# FMB_MOS.net
KiCad netlist of a schematic drawn in Altium Designer
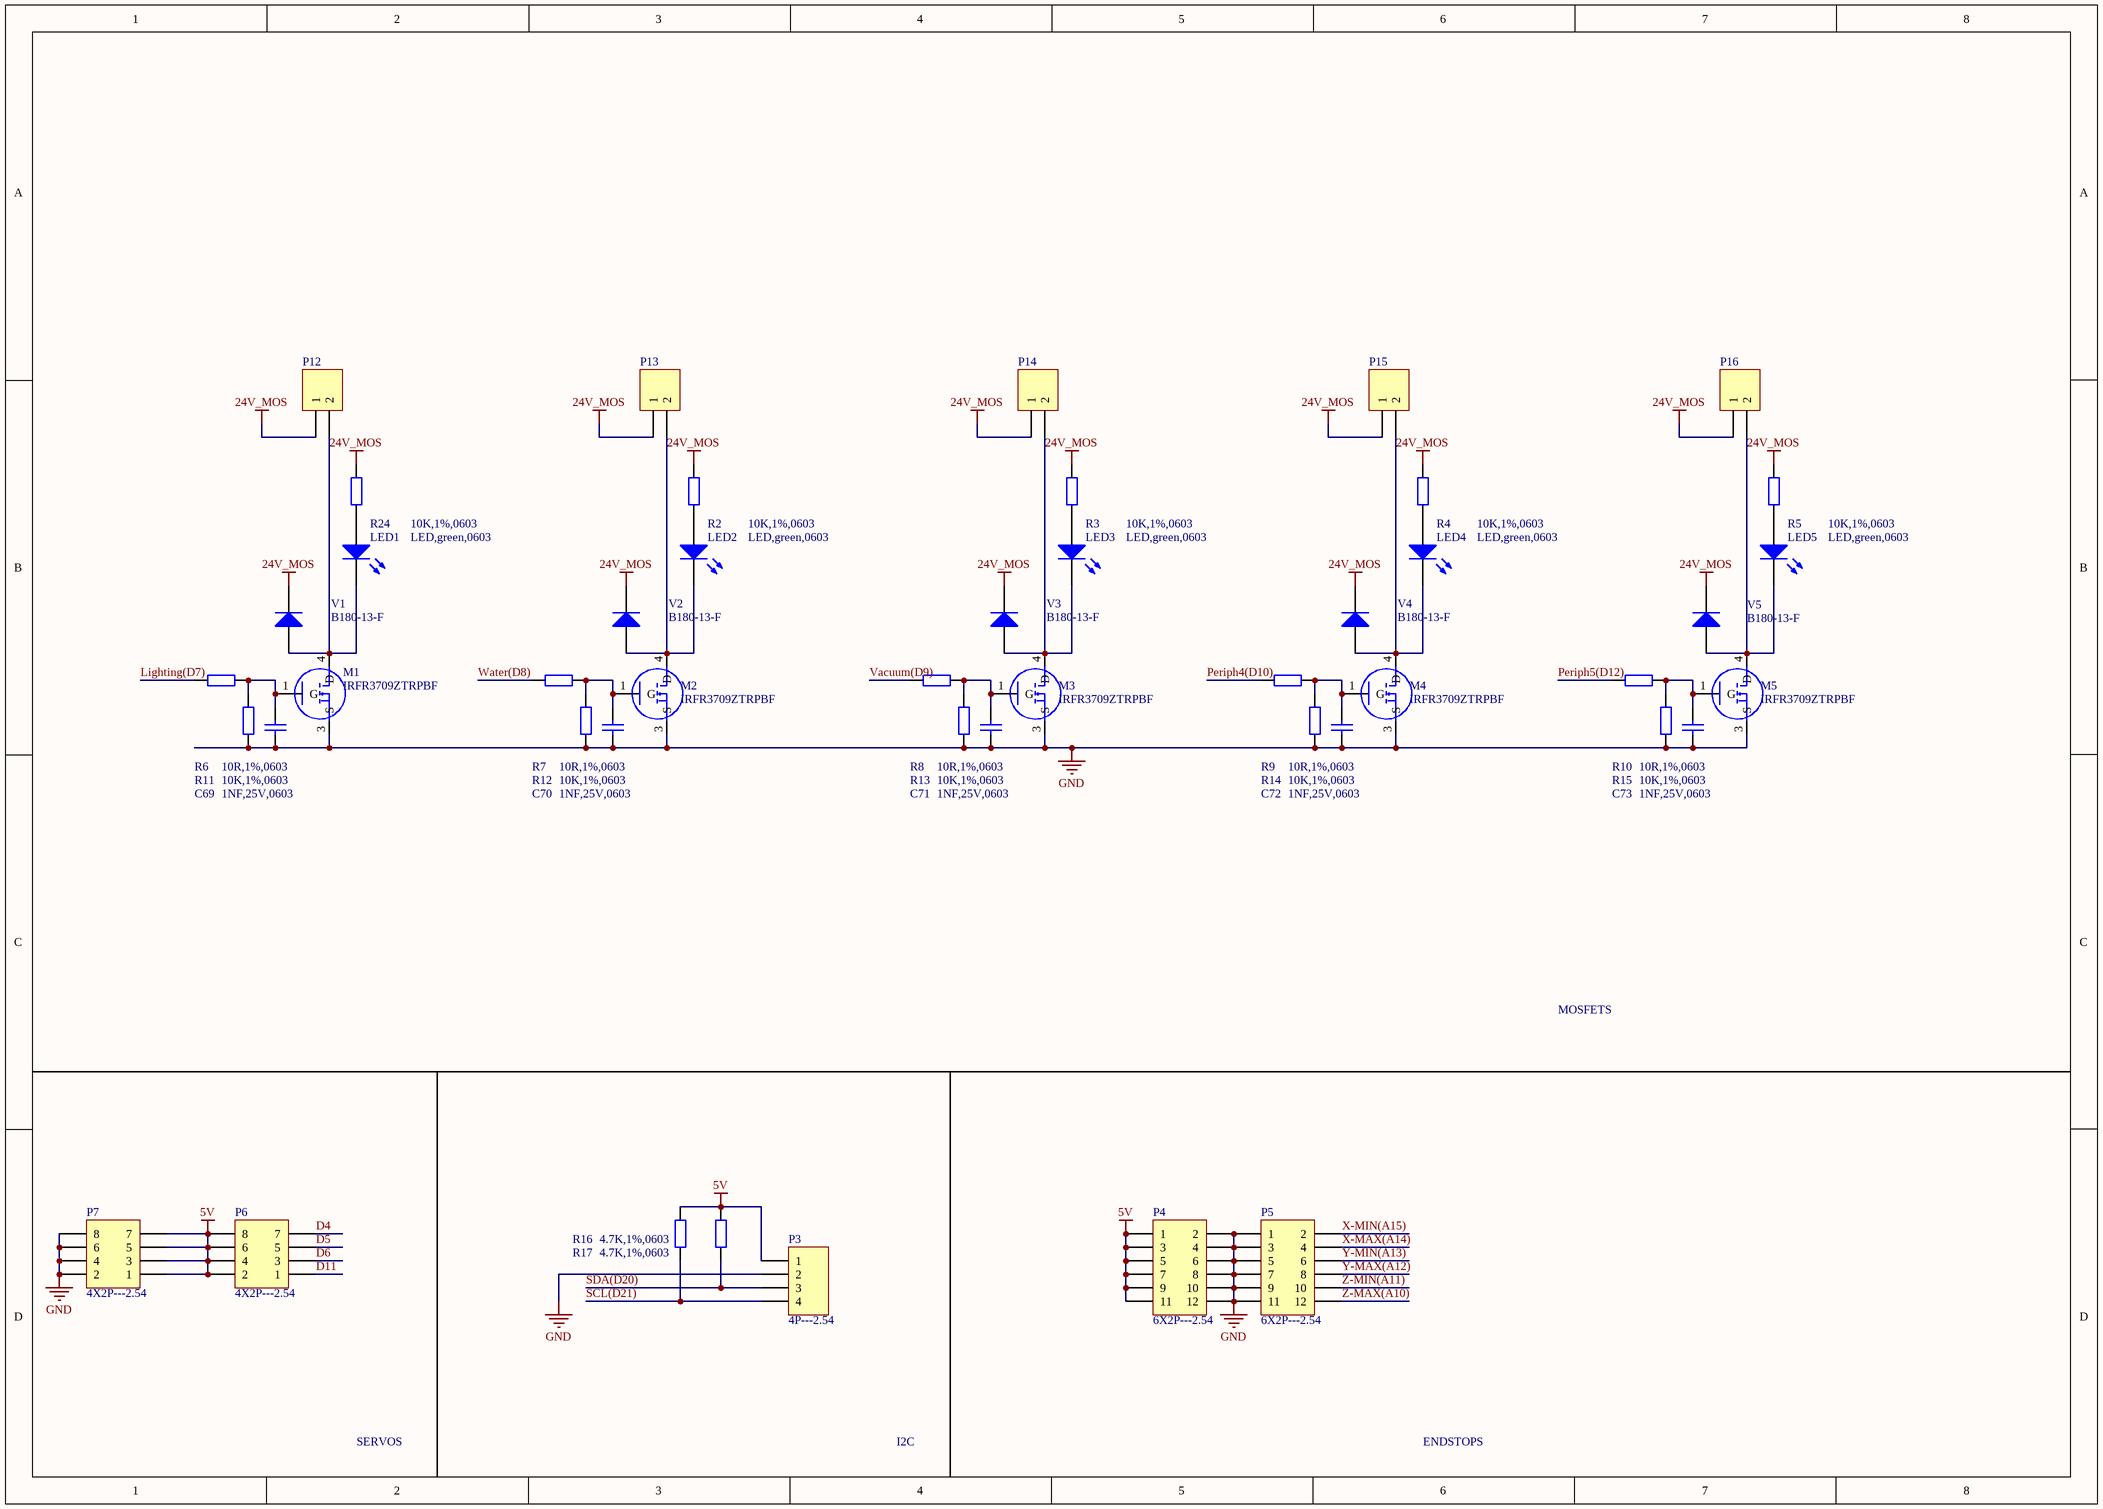
[diagram p0: FMB_MOS.SchDoc]

(export (version "E")
  (design (tool "Eeschema 10.0.6"))
  (components
    (comp (ref "C69")
      (value "1NF,25V,0603")
      (footprint "RC0603")
      (description "Capacitor")
      (fields (field (name "PUBLISHER") "Altium Limited"))
      (libsource (lib "Miscellaneous Devices") (part "Cap"))
    )
    (comp (ref "C70")
      (value "1NF,25V,0603")
      (footprint "RC0603")
      (description "Capacitor")
      (fields (field (name "PUBLISHER") "Altium Limited"))
      (libsource (lib "Miscellaneous Devices") (part "Cap"))
    )
    (comp (ref "C71")
      (value "1NF,25V,0603")
      (footprint "RC0603")
      (description "Capacitor")
      (fields (field (name "PUBLISHER") "Altium Limited"))
      (libsource (lib "Miscellaneous Devices") (part "Cap"))
    )
    (comp (ref "C72")
      (value "1NF,25V,0603")
      (footprint "RC0603")
      (description "Capacitor")
      (fields (field (name "PUBLISHER") "Altium Limited"))
      (libsource (lib "Miscellaneous Devices") (part "Cap"))
    )
    (comp (ref "C73")
      (value "1NF,25V,0603")
      (footprint "RC0603")
      (description "Capacitor")
      (fields (field (name "PUBLISHER") "Altium Limited"))
      (libsource (lib "Miscellaneous Devices") (part "Cap"))
    )
    (comp (ref "LED1")
      (value "LED,green,0603")
      (footprint "LED-0603")
      (description "Typical INFRARED GaAs LED")
      (fields (field (name "PUBLISHER") "Altium Limited"))
      (libsource (lib "Miscellaneous Devices") (part "LED0"))
    )
    (comp (ref "LED2")
      (value "LED,green,0603")
      (footprint "LED-0603")
      (description "Typical INFRARED GaAs LED")
      (fields (field (name "PUBLISHER") "Altium Limited"))
      (libsource (lib "Miscellaneous Devices") (part "LED0"))
    )
    (comp (ref "LED3")
      (value "LED,green,0603")
      (footprint "LED-0603")
      (description "Typical INFRARED GaAs LED")
      (fields (field (name "PUBLISHER") "Altium Limited"))
      (libsource (lib "Miscellaneous Devices") (part "LED0"))
    )
    (comp (ref "LED4")
      (value "LED,green,0603")
      (footprint "LED-0603")
      (description "Typical INFRARED GaAs LED")
      (fields (field (name "PUBLISHER") "Altium Limited"))
      (libsource (lib "Miscellaneous Devices") (part "LED0"))
    )
    (comp (ref "LED5")
      (value "LED,green,0603")
      (footprint "LED-0603")
      (description "Typical INFRARED GaAs LED")
      (fields (field (name "PUBLISHER") "Altium Limited"))
      (libsource (lib "Miscellaneous Devices") (part "LED0"))
    )
    (comp (ref "M1") (value "IRFR3709ZTRPBF") (footprint "DPAK") (libsource (lib "AP94T07") (part "AP94T07")))
    (comp (ref "M2") (value "IRFR3709ZTRPBF") (footprint "DPAK") (libsource (lib "AP94T07") (part "AP94T07")))
    (comp (ref "M3") (value "IRFR3709ZTRPBF") (footprint "DPAK") (libsource (lib "AP94T07") (part "AP94T07")))
    (comp (ref "M4") (value "IRFR3709ZTRPBF") (footprint "DPAK") (libsource (lib "AP94T07") (part "AP94T07")))
    (comp (ref "M5") (value "IRFR3709ZTRPBF") (footprint "DPAK") (libsource (lib "AP94T07") (part "AP94T07")))
    (comp (ref "P3")
      (value "4P---2.54")
      (footprint "HDR1X4")
      (description "Header, 4-Pin")
      (fields (field (name "PUBLISHER") "Altium Limited"))
      (libsource (lib "Miscellaneous Connectors") (part "Header 4"))
    )
    (comp (ref "P4")
      (value "6X2P---2.54")
      (footprint "HDR2X6")
      (description "Header, 6-Pin, Dual row")
      (fields (field (name "PUBLISHER") "Altium Limited"))
      (libsource (lib "Miscellaneous Connectors") (part "Header 6X2"))
    )
    (comp (ref "P5")
      (value "6X2P---2.54")
      (footprint "HDR2X6")
      (description "Header, 6-Pin, Dual row")
      (fields (field (name "PUBLISHER") "Altium Limited"))
      (libsource (lib "Miscellaneous Connectors") (part "Header 6X2"))
    )
    (comp (ref "P6")
      (value "4X2P---2.54")
      (footprint "HDR2X4")
      (description "Header, 4-Pin, Dual row")
      (fields (field (name "PUBLISHER") "Altium Limited"))
      (libsource (lib "Miscellaneous Connectors") (part "Header 4X2"))
    )
    (comp (ref "P7")
      (value "4X2P---2.54")
      (footprint "HDR2X4")
      (description "Header, 4-Pin, Dual row")
      (fields (field (name "PUBLISHER") "Altium Limited"))
      (libsource (lib "Miscellaneous Connectors") (part "Header 4X2"))
    )
    (comp (ref "P12")
      (value "Molex 151048-1206")
      (footprint "151048")
      (description "Header, 2-Pin")
      (fields (field (name "PUBLISHER") "Altium Limited"))
      (libsource (lib "Miscellaneous Connectors") (part "Header 2"))
    )
    (comp (ref "P13")
      (value "Molex 151048-1206")
      (footprint "151048")
      (description "Header, 2-Pin")
      (fields (field (name "PUBLISHER") "Altium Limited"))
      (libsource (lib "Miscellaneous Connectors") (part "Header 2"))
    )
    (comp (ref "P14")
      (value "Molex 151048-1206")
      (footprint "151048")
      (description "Header, 2-Pin")
      (fields (field (name "PUBLISHER") "Altium Limited"))
      (libsource (lib "Miscellaneous Connectors") (part "Header 2"))
    )
    (comp (ref "P15")
      (value "Molex 151048-1206")
      (footprint "151048")
      (description "Header, 2-Pin")
      (fields (field (name "PUBLISHER") "Altium Limited"))
      (libsource (lib "Miscellaneous Connectors") (part "Header 2"))
    )
    (comp (ref "P16")
      (value "Molex 151048-1206")
      (footprint "151048")
      (description "Header, 2-Pin")
      (fields (field (name "PUBLISHER") "Altium Limited"))
      (libsource (lib "Miscellaneous Connectors") (part "Header 2"))
    )
    (comp (ref "R2")
      (value "10K,1%,0603")
      (footprint "RC0603")
      (description "Resistor")
      (fields (field (name "PUBLISHER") "Altium Limited"))
      (libsource (lib "") (part "Res2_1"))
    )
    (comp (ref "R3")
      (value "10K,1%,0603")
      (footprint "RC0603")
      (description "Resistor")
      (fields (field (name "PUBLISHER") "Altium Limited"))
      (libsource (lib "") (part "Res2_1"))
    )
    (comp (ref "R4")
      (value "10K,1%,0603")
      (footprint "RC0603")
      (description "Resistor")
      (fields (field (name "PUBLISHER") "Altium Limited"))
      (libsource (lib "") (part "Res2_1"))
    )
    (comp (ref "R5")
      (value "10K,1%,0603")
      (footprint "RC0603")
      (description "Resistor")
      (fields (field (name "PUBLISHER") "Altium Limited"))
      (libsource (lib "") (part "Res2_1"))
    )
    (comp (ref "R6")
      (value "10R,1%,0603")
      (footprint "RC0603")
      (description "Resistor")
      (fields (field (name "PUBLISHER") "Altium Limited"))
      (libsource (lib "") (part "Res2_2"))
    )
    (comp (ref "R7")
      (value "10R,1%,0603")
      (footprint "RC0603")
      (description "Resistor")
      (fields (field (name "PUBLISHER") "Altium Limited"))
      (libsource (lib "") (part "Res2_2"))
    )
    (comp (ref "R8")
      (value "10R,1%,0603")
      (footprint "RC0603")
      (description "Resistor")
      (fields (field (name "PUBLISHER") "Altium Limited"))
      (libsource (lib "") (part "Res2_2"))
    )
    (comp (ref "R9")
      (value "10R,1%,0603")
      (footprint "RC0603")
      (description "Resistor")
      (fields (field (name "PUBLISHER") "Altium Limited"))
      (libsource (lib "") (part "Res2_2"))
    )
    (comp (ref "R10")
      (value "10R,1%,0603")
      (footprint "RC0603")
      (description "Resistor")
      (fields (field (name "PUBLISHER") "Altium Limited"))
      (libsource (lib "") (part "Res2_2"))
    )
    (comp (ref "R11")
      (value "10K,1%,0603")
      (footprint "RC0603")
      (description "Resistor")
      (fields (field (name "PUBLISHER") "Altium Limited"))
      (libsource (lib "Miscellaneous Devices") (part "Res2"))
    )
    (comp (ref "R12")
      (value "10K,1%,0603")
      (footprint "RC0603")
      (description "Resistor")
      (fields (field (name "PUBLISHER") "Altium Limited"))
      (libsource (lib "Miscellaneous Devices") (part "Res2"))
    )
    (comp (ref "R13")
      (value "10K,1%,0603")
      (footprint "RC0603")
      (description "Resistor")
      (fields (field (name "PUBLISHER") "Altium Limited"))
      (libsource (lib "") (part "Res2_1"))
    )
    (comp (ref "R14")
      (value "10K,1%,0603")
      (footprint "RC0603")
      (description "Resistor")
      (fields (field (name "PUBLISHER") "Altium Limited"))
      (libsource (lib "Miscellaneous Devices") (part "Res2"))
    )
    (comp (ref "R15")
      (value "10K,1%,0603")
      (footprint "RC0603")
      (description "Resistor")
      (fields (field (name "PUBLISHER") "Altium Limited"))
      (libsource (lib "Miscellaneous Devices") (part "Res2"))
    )
    (comp (ref "R16")
      (value "4.7K,1%,0603")
      (footprint "RC0603")
      (description "Resistor")
      (fields (field (name "PUBLISHER") "Altium Limited"))
      (libsource (lib "Miscellaneous Devices") (part "Res2"))
    )
    (comp (ref "R17")
      (value "4.7K,1%,0603")
      (footprint "RC0603")
      (description "Resistor")
      (fields (field (name "PUBLISHER") "Altium Limited"))
      (libsource (lib "Miscellaneous Devices") (part "Res2"))
    )
    (comp (ref "R24")
      (value "10K,1%,0603")
      (footprint "RC0603")
      (description "Resistor")
      (fields (field (name "PUBLISHER") "Altium Limited"))
      (libsource (lib "") (part "Res2_1"))
    )
    (comp (ref "V1")
      (value "B180-13-F")
      (footprint "SMA")
      (description "Default Diode")
      (fields (field (name "PUBLISHER") "Altium Limited"))
      (libsource (lib "Miscellaneous Devices") (part "Diode"))
    )
    (comp (ref "V2")
      (value "B180-13-F")
      (footprint "SMA")
      (description "Default Diode")
      (fields (field (name "PUBLISHER") "Altium Limited"))
      (libsource (lib "Miscellaneous Devices") (part "Diode"))
    )
    (comp (ref "V3")
      (value "B180-13-F")
      (footprint "SMA")
      (description "Default Diode")
      (fields (field (name "PUBLISHER") "Altium Limited"))
      (libsource (lib "Miscellaneous Devices") (part "Diode"))
    )
    (comp (ref "V4")
      (value "B180-13-F")
      (footprint "SMA")
      (description "Default Diode")
      (fields (field (name "PUBLISHER") "Altium Limited"))
      (libsource (lib "Miscellaneous Devices") (part "Diode"))
    )
    (comp (ref "V5")
      (value "B180-13-F")
      (footprint "SMA")
      (description "Default Diode")
      (fields (field (name "PUBLISHER") "Altium Limited"))
      (libsource (lib "Miscellaneous Devices") (part "Diode"))
    )
  )
  (nets
    (net (code "1") (name "/D4") (class "Default")
      (node (ref "P6") (pin "7") (pinfunction "7_7") (pintype "passive"))
    )
    (net (code "2") (name "/D5") (class "Default")
      (node (ref "P6") (pin "5") (pinfunction "5_5") (pintype "passive"))
    )
    (net (code "3") (name "/D6") (class "Default")
      (node (ref "P6") (pin "3") (pinfunction "3_3") (pintype "passive"))
    )
    (net (code "4") (name "/D11") (class "Default")
      (node (ref "P6") (pin "1") (pinfunction "1_1") (pintype "passive"))
    )
    (net (code "5") (name "/Lighting(D7)") (class "Default")
      (node (ref "R6") (pin "1") (pinfunction "1_1") (pintype "passive"))
    )
    (net (code "6") (name "/Periph4(D10)") (class "Default")
      (node (ref "R9") (pin "1") (pinfunction "1_1") (pintype "passive"))
    )
    (net (code "7") (name "/Periph5(D12)") (class "Default")
      (node (ref "R10") (pin "1") (pinfunction "1_1") (pintype "passive"))
    )
    (net (code "8") (name "/SCL(D21)") (class "Default")
      (node (ref "P3") (pin "4") (pinfunction "4_4") (pintype "passive"))
      (node (ref "R16") (pin "1") (pinfunction "1_1") (pintype "passive"))
    )
    (net (code "9") (name "/SDA(D20)") (class "Default")
      (node (ref "P3") (pin "3") (pinfunction "3_3") (pintype "passive"))
      (node (ref "R17") (pin "1") (pinfunction "1_1") (pintype "passive"))
    )
    (net (code "10") (name "/Vacuum(D9)") (class "Default")
      (node (ref "R8") (pin "1") (pinfunction "1_1") (pintype "passive"))
    )
    (net (code "11") (name "/Water(D8)") (class "Default")
      (node (ref "R7") (pin "1") (pinfunction "1_1") (pintype "passive"))
    )
    (net (code "12") (name "/X-MAX(A14)") (class "Default")
      (node (ref "P5") (pin "4") (pinfunction "4_4") (pintype "passive"))
    )
    (net (code "13") (name "/X-MIN(A15)") (class "Default")
      (node (ref "P5") (pin "2") (pinfunction "2_2") (pintype "passive"))
    )
    (net (code "14") (name "/Y-MAX(A12)") (class "Default")
      (node (ref "P5") (pin "8") (pinfunction "8_8") (pintype "passive"))
    )
    (net (code "15") (name "/Y-MIN(A13)") (class "Default")
      (node (ref "P5") (pin "6") (pinfunction "6_6") (pintype "passive"))
    )
    (net (code "16") (name "/Z-MAX(A10)") (class "Default")
      (node (ref "P5") (pin "12") (pinfunction "12_12") (pintype "passive"))
    )
    (net (code "17") (name "/Z-MIN(A11)") (class "Default")
      (node (ref "P5") (pin "10") (pinfunction "10_10") (pintype "passive"))
    )
    (net (code "18") (name "5V") (class "Default")
      (node (ref "P3") (pin "1") (pinfunction "1_1") (pintype "passive"))
      (node (ref "P4") (pin "1") (pinfunction "1_1") (pintype "passive"))
      (node (ref "P4") (pin "11") (pinfunction "11_11") (pintype "passive"))
      (node (ref "P4") (pin "3") (pinfunction "3_3") (pintype "passive"))
      (node (ref "P4") (pin "5") (pinfunction "5_5") (pintype "passive"))
      (node (ref "P4") (pin "7") (pinfunction "7_7") (pintype "passive"))
      (node (ref "P4") (pin "9") (pinfunction "9_9") (pintype "passive"))
      (node (ref "P6") (pin "2") (pinfunction "2_2") (pintype "passive"))
      (node (ref "P6") (pin "4") (pinfunction "4_4") (pintype "passive"))
      (node (ref "P6") (pin "6") (pinfunction "6_6") (pintype "passive"))
      (node (ref "P6") (pin "8") (pinfunction "8_8") (pintype "passive"))
      (node (ref "P7") (pin "1") (pinfunction "1_1") (pintype "passive"))
      (node (ref "P7") (pin "3") (pinfunction "3_3") (pintype "passive"))
      (node (ref "P7") (pin "5") (pinfunction "5_5") (pintype "passive"))
      (node (ref "P7") (pin "7") (pinfunction "7_7") (pintype "passive"))
      (node (ref "R16") (pin "2") (pinfunction "2_2") (pintype "passive"))
      (node (ref "R17") (pin "2") (pinfunction "2_2") (pintype "passive"))
    )
    (net (code "19") (name "24V_MOS") (class "Default")
      (node (ref "P12") (pin "1") (pinfunction "1_1") (pintype "passive"))
      (node (ref "P13") (pin "1") (pinfunction "1_1") (pintype "passive"))
      (node (ref "P14") (pin "1") (pinfunction "1_1") (pintype "passive"))
      (node (ref "P15") (pin "1") (pinfunction "1_1") (pintype "passive"))
      (node (ref "P16") (pin "1") (pinfunction "1_1") (pintype "passive"))
      (node (ref "R2") (pin "1") (pinfunction "1_1") (pintype "passive"))
      (node (ref "R24") (pin "1") (pinfunction "1_1") (pintype "passive"))
      (node (ref "R3") (pin "1") (pinfunction "1_1") (pintype "passive"))
      (node (ref "R4") (pin "1") (pinfunction "1_1") (pintype "passive"))
      (node (ref "R5") (pin "1") (pinfunction "1_1") (pintype "passive"))
      (node (ref "V1") (pin "2") (pinfunction "K_2") (pintype "passive"))
      (node (ref "V2") (pin "2") (pinfunction "K_2") (pintype "passive"))
      (node (ref "V3") (pin "2") (pinfunction "K_2") (pintype "passive"))
      (node (ref "V4") (pin "2") (pinfunction "K_2") (pintype "passive"))
      (node (ref "V5") (pin "2") (pinfunction "K_2") (pintype "passive"))
    )
    (net (code "20") (name "GND") (class "Default")
      (node (ref "C69") (pin "1") (pinfunction "1_1") (pintype "passive"))
      (node (ref "C70") (pin "1") (pinfunction "1_1") (pintype "passive"))
      (node (ref "C71") (pin "1") (pinfunction "1_1") (pintype "passive"))
      (node (ref "C72") (pin "1") (pinfunction "1_1") (pintype "passive"))
      (node (ref "C73") (pin "1") (pinfunction "1_1") (pintype "passive"))
      (node (ref "M1") (pin "3") (pinfunction "S_3") (pintype "passive"))
      (node (ref "M2") (pin "3") (pinfunction "S_3") (pintype "passive"))
      (node (ref "M3") (pin "3") (pinfunction "S_3") (pintype "passive"))
      (node (ref "M4") (pin "3") (pinfunction "S_3") (pintype "passive"))
      (node (ref "M5") (pin "3") (pinfunction "S_3") (pintype "passive"))
      (node (ref "P3") (pin "2") (pinfunction "2_2") (pintype "passive"))
      (node (ref "P4") (pin "10") (pinfunction "10_10") (pintype "passive"))
      (node (ref "P4") (pin "12") (pinfunction "12_12") (pintype "passive"))
      (node (ref "P4") (pin "2") (pinfunction "2_2") (pintype "passive"))
      (node (ref "P4") (pin "4") (pinfunction "4_4") (pintype "passive"))
      (node (ref "P4") (pin "6") (pinfunction "6_6") (pintype "passive"))
      (node (ref "P4") (pin "8") (pinfunction "8_8") (pintype "passive"))
      (node (ref "P5") (pin "1") (pinfunction "1_1") (pintype "passive"))
      (node (ref "P5") (pin "11") (pinfunction "11_11") (pintype "passive"))
      (node (ref "P5") (pin "3") (pinfunction "3_3") (pintype "passive"))
      (node (ref "P5") (pin "5") (pinfunction "5_5") (pintype "passive"))
      (node (ref "P5") (pin "7") (pinfunction "7_7") (pintype "passive"))
      (node (ref "P5") (pin "9") (pinfunction "9_9") (pintype "passive"))
      (node (ref "P7") (pin "2") (pinfunction "2_2") (pintype "passive"))
      (node (ref "P7") (pin "4") (pinfunction "4_4") (pintype "passive"))
      (node (ref "P7") (pin "6") (pinfunction "6_6") (pintype "passive"))
      (node (ref "P7") (pin "8") (pinfunction "8_8") (pintype "passive"))
      (node (ref "R11") (pin "1") (pinfunction "1_1") (pintype "passive"))
      (node (ref "R12") (pin "1") (pinfunction "1_1") (pintype "passive"))
      (node (ref "R13") (pin "2") (pinfunction "2_2") (pintype "passive"))
      (node (ref "R14") (pin "1") (pinfunction "1_1") (pintype "passive"))
      (node (ref "R15") (pin "1") (pinfunction "1_1") (pintype "passive"))
    )
    (net (code "21") (name "Net-(LED1-A)") (class "Default")
      (node (ref "LED1") (pin "1") (pinfunction "A_1") (pintype "passive"))
      (node (ref "R24") (pin "2") (pinfunction "2_2") (pintype "passive"))
    )
    (net (code "22") (name "Net-(LED1-K)") (class "Default")
      (node (ref "LED1") (pin "2") (pinfunction "K_2") (pintype "passive"))
      (node (ref "M1") (pin "4") (pinfunction "D_4") (pintype "passive"))
      (node (ref "P12") (pin "2") (pinfunction "2_2") (pintype "passive"))
      (node (ref "V1") (pin "1") (pinfunction "A_1") (pintype "passive"))
    )
    (net (code "23") (name "Net-(LED2-A)") (class "Default")
      (node (ref "LED2") (pin "1") (pinfunction "A_1") (pintype "passive"))
      (node (ref "R2") (pin "2") (pinfunction "2_2") (pintype "passive"))
    )
    (net (code "24") (name "Net-(LED2-K)") (class "Default")
      (node (ref "LED2") (pin "2") (pinfunction "K_2") (pintype "passive"))
      (node (ref "M2") (pin "4") (pinfunction "D_4") (pintype "passive"))
      (node (ref "P13") (pin "2") (pinfunction "2_2") (pintype "passive"))
      (node (ref "V2") (pin "1") (pinfunction "A_1") (pintype "passive"))
    )
    (net (code "25") (name "Net-(LED3-A)") (class "Default")
      (node (ref "LED3") (pin "1") (pinfunction "A_1") (pintype "passive"))
      (node (ref "R3") (pin "2") (pinfunction "2_2") (pintype "passive"))
    )
    (net (code "26") (name "Net-(LED3-K)") (class "Default")
      (node (ref "LED3") (pin "2") (pinfunction "K_2") (pintype "passive"))
      (node (ref "M3") (pin "4") (pinfunction "D_4") (pintype "passive"))
      (node (ref "P14") (pin "2") (pinfunction "2_2") (pintype "passive"))
      (node (ref "V3") (pin "1") (pinfunction "A_1") (pintype "passive"))
    )
    (net (code "27") (name "Net-(LED4-A)") (class "Default")
      (node (ref "LED4") (pin "1") (pinfunction "A_1") (pintype "passive"))
      (node (ref "R4") (pin "2") (pinfunction "2_2") (pintype "passive"))
    )
    (net (code "28") (name "Net-(LED4-K)") (class "Default")
      (node (ref "LED4") (pin "2") (pinfunction "K_2") (pintype "passive"))
      (node (ref "M4") (pin "4") (pinfunction "D_4") (pintype "passive"))
      (node (ref "P15") (pin "2") (pinfunction "2_2") (pintype "passive"))
      (node (ref "V4") (pin "1") (pinfunction "A_1") (pintype "passive"))
    )
    (net (code "29") (name "Net-(LED5-A)") (class "Default")
      (node (ref "LED5") (pin "1") (pinfunction "A_1") (pintype "passive"))
      (node (ref "R5") (pin "2") (pinfunction "2_2") (pintype "passive"))
    )
    (net (code "30") (name "Net-(LED5-K)") (class "Default")
      (node (ref "LED5") (pin "2") (pinfunction "K_2") (pintype "passive"))
      (node (ref "M5") (pin "4") (pinfunction "D_4") (pintype "passive"))
      (node (ref "P16") (pin "2") (pinfunction "2_2") (pintype "passive"))
      (node (ref "V5") (pin "1") (pinfunction "A_1") (pintype "passive"))
    )
    (net (code "31") (name "Net-(M1-G)") (class "Default")
      (node (ref "C69") (pin "2") (pinfunction "2_2") (pintype "passive"))
      (node (ref "M1") (pin "1") (pinfunction "G_1") (pintype "passive"))
      (node (ref "R11") (pin "2") (pinfunction "2_2") (pintype "passive"))
      (node (ref "R6") (pin "2") (pinfunction "2_2") (pintype "passive"))
    )
    (net (code "32") (name "Net-(M2-G)") (class "Default")
      (node (ref "C70") (pin "2") (pinfunction "2_2") (pintype "passive"))
      (node (ref "M2") (pin "1") (pinfunction "G_1") (pintype "passive"))
      (node (ref "R12") (pin "2") (pinfunction "2_2") (pintype "passive"))
      (node (ref "R7") (pin "2") (pinfunction "2_2") (pintype "passive"))
    )
    (net (code "33") (name "Net-(M3-G)") (class "Default")
      (node (ref "C71") (pin "2") (pinfunction "2_2") (pintype "passive"))
      (node (ref "M3") (pin "1") (pinfunction "G_1") (pintype "passive"))
      (node (ref "R13") (pin "1") (pinfunction "1_1") (pintype "passive"))
      (node (ref "R8") (pin "2") (pinfunction "2_2") (pintype "passive"))
    )
    (net (code "34") (name "Net-(M4-G)") (class "Default")
      (node (ref "C72") (pin "2") (pinfunction "2_2") (pintype "passive"))
      (node (ref "M4") (pin "1") (pinfunction "G_1") (pintype "passive"))
      (node (ref "R14") (pin "2") (pinfunction "2_2") (pintype "passive"))
      (node (ref "R9") (pin "2") (pinfunction "2_2") (pintype "passive"))
    )
    (net (code "35") (name "Net-(M5-G)") (class "Default")
      (node (ref "C73") (pin "2") (pinfunction "2_2") (pintype "passive"))
      (node (ref "M5") (pin "1") (pinfunction "G_1") (pintype "passive"))
      (node (ref "R10") (pin "2") (pinfunction "2_2") (pintype "passive"))
      (node (ref "R15") (pin "2") (pinfunction "2_2") (pintype "passive"))
    )
  )
)
